# module-mp7740.net
KiCad netlist of a schematic drawn in EAGLE
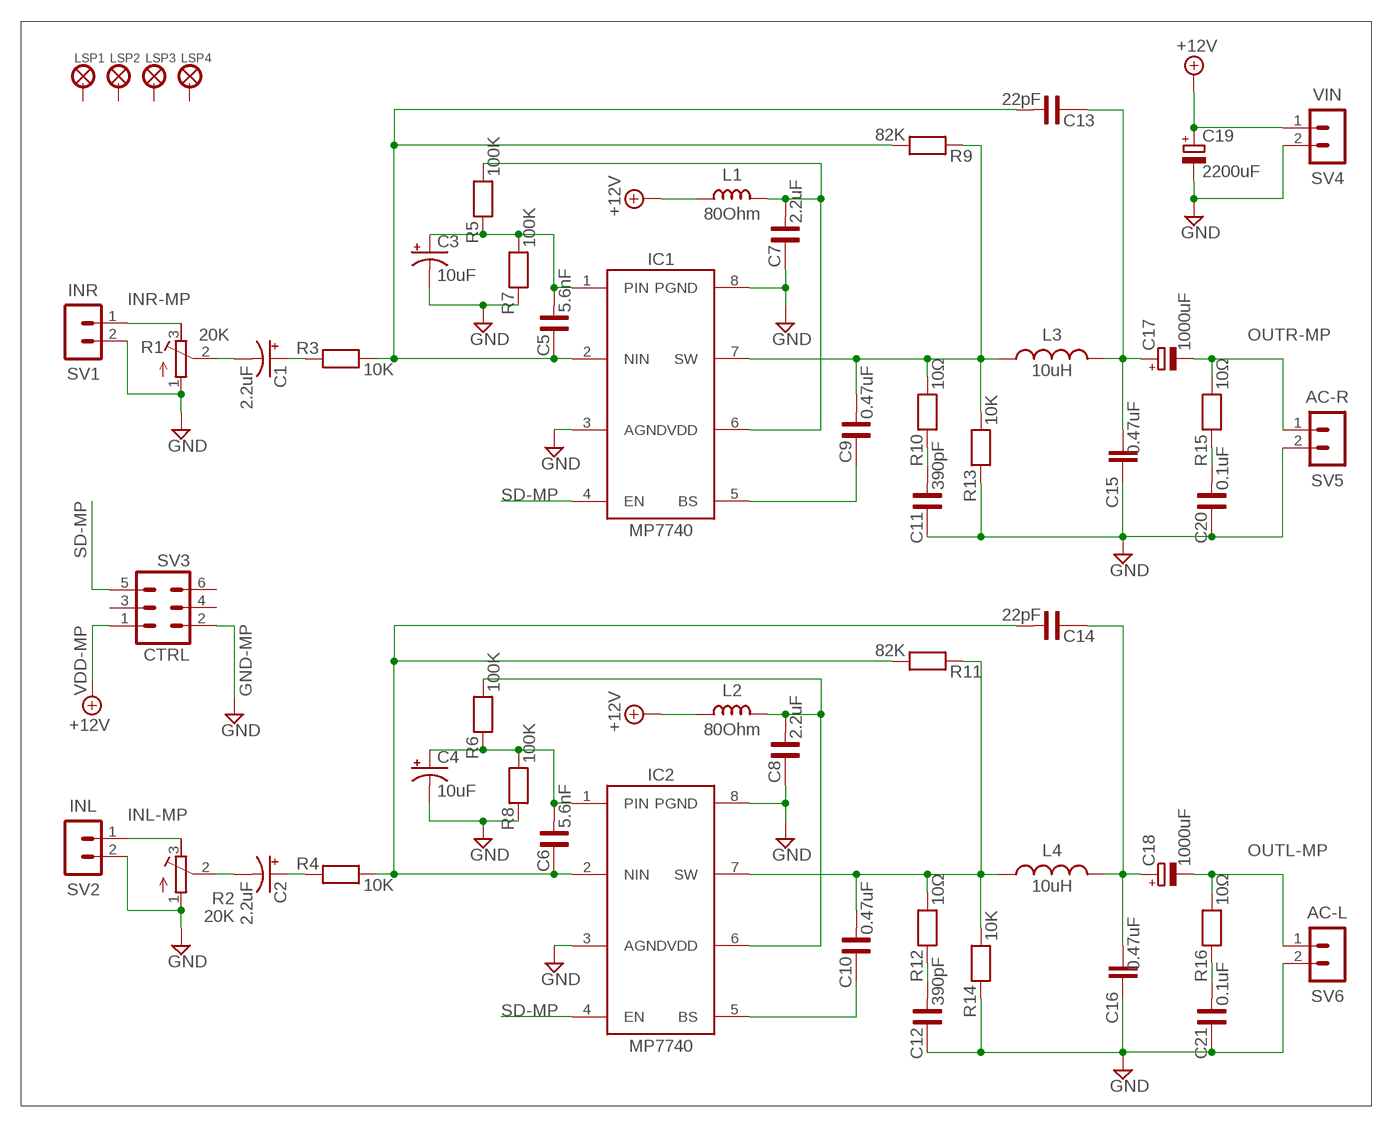
[diagram p0: schematic, sheet 1]

(export (version "E")
  (design (tool "Eeschema 10.0.6"))
  (components
    (comp (ref "C1")
      (value "2.2uF")
      (footprint "eagle-import:E2-5")
      (libsource (lib "eagle-import") (part "CPOL-USE2-5"))
    )
    (comp (ref "C2")
      (value "2.2uF")
      (footprint "eagle-import:E2-5")
      (libsource (lib "eagle-import") (part "CPOL-USE2-5"))
    )
    (comp (ref "C3")
      (value "10uF")
      (footprint "eagle-import:E2-5")
      (libsource (lib "eagle-import") (part "CPOL-USE2-5"))
    )
    (comp (ref "C4")
      (value "10uF")
      (footprint "eagle-import:E2-5")
      (libsource (lib "eagle-import") (part "CPOL-USE2-5"))
    )
    (comp (ref "C5")
      (value "5.6nF")
      (footprint "eagle-import:C0805")
      (libsource (lib "eagle-import") (part "C-US0805"))
    )
    (comp (ref "C6")
      (value "5.6nF")
      (footprint "eagle-import:C0805")
      (libsource (lib "eagle-import") (part "C-US0805"))
    )
    (comp (ref "C7")
      (value "2.2uF")
      (footprint "eagle-import:C1206")
      (libsource (lib "eagle-import") (part "C-US1206"))
    )
    (comp (ref "C8")
      (value "2.2uF")
      (footprint "eagle-import:C1206")
      (libsource (lib "eagle-import") (part "C-US1206"))
    )
    (comp (ref "C9")
      (value "0.47uF")
      (footprint "eagle-import:C0805")
      (libsource (lib "eagle-import") (part "C-US0805"))
    )
    (comp (ref "C10")
      (value "0.47uF")
      (footprint "eagle-import:C0805")
      (libsource (lib "eagle-import") (part "C-US0805"))
    )
    (comp (ref "C11")
      (value "390pF")
      (footprint "eagle-import:C0805")
      (libsource (lib "eagle-import") (part "C-US0805"))
    )
    (comp (ref "C12")
      (value "390pF")
      (footprint "eagle-import:C0805")
      (libsource (lib "eagle-import") (part "C-US0805"))
    )
    (comp (ref "C13")
      (value "22pF")
      (footprint "eagle-import:C0805")
      (libsource (lib "eagle-import") (part "C-US0805"))
    )
    (comp (ref "C14")
      (value "22pF")
      (footprint "eagle-import:C0805")
      (libsource (lib "eagle-import") (part "C-US0805"))
    )
    (comp (ref "C15")
      (value "0.47uF")
      (footprint "eagle-import:C050-050X075")
      (libsource (lib "eagle-import") (part "C-EU050-050X075"))
    )
    (comp (ref "C16")
      (value "0.47uF")
      (footprint "eagle-import:C050-050X075")
      (libsource (lib "eagle-import") (part "C-EU050-050X075"))
    )
    (comp (ref "C17")
      (value "1000uF")
      (footprint "eagle-import:E5-13")
      (libsource (lib "eagle-import") (part "CPOL-EUE5-13"))
    )
    (comp (ref "C18")
      (value "1000uF")
      (footprint "eagle-import:E5-13")
      (libsource (lib "eagle-import") (part "CPOL-EUE5-13"))
    )
    (comp (ref "C19")
      (value "2200uF")
      (footprint "eagle-import:E7,5-16")
      (libsource (lib "eagle-import") (part "CPOL-EUE7.5-16"))
    )
    (comp (ref "C20")
      (value "0.1uF")
      (footprint "eagle-import:C0805")
      (libsource (lib "eagle-import") (part "C-US0805"))
    )
    (comp (ref "C21")
      (value "0.1uF")
      (footprint "eagle-import:C0805")
      (libsource (lib "eagle-import") (part "C-US0805"))
    )
    (comp (ref "IC1")
      (value "MP7740")
      (footprint "eagle-import:SOIC-8")
      (libsource (lib "eagle-import") (part "MP7740"))
    )
    (comp (ref "IC2")
      (value "MP7740")
      (footprint "eagle-import:SOIC-8")
      (libsource (lib "eagle-import") (part "MP7740"))
    )
    (comp (ref "L1")
      (value "80Ohm")
      (footprint "eagle-import:L0805")
      (libsource (lib "eagle-import") (part "L-USL0805"))
    )
    (comp (ref "L2")
      (value "80Ohm")
      (footprint "eagle-import:L0805")
      (libsource (lib "eagle-import") (part "L-USL0805"))
    )
    (comp (ref "L3")
      (value "10uH")
      (footprint "eagle-import:6000-XXXX-RC")
      (libsource (lib "eagle-import") (part "L-US6000-XXX-RC"))
    )
    (comp (ref "L4")
      (value "10uH")
      (footprint "eagle-import:6000-XXXX-RC")
      (libsource (lib "eagle-import") (part "L-US6000-XXX-RC"))
    )
    (comp (ref "LSP1")
      (value "LSP27")
      (footprint "eagle-import:LSP27")
      (libsource (lib "eagle-import") (part "LSP27"))
    )
    (comp (ref "LSP2")
      (value "LSP27")
      (footprint "eagle-import:LSP27")
      (libsource (lib "eagle-import") (part "LSP27"))
    )
    (comp (ref "LSP3")
      (value "LSP27")
      (footprint "eagle-import:LSP27")
      (libsource (lib "eagle-import") (part "LSP27"))
    )
    (comp (ref "LSP4")
      (value "LSP27")
      (footprint "eagle-import:LSP27")
      (libsource (lib "eagle-import") (part "LSP27"))
    )
    (comp (ref "R1")
      (value "20K")
      (footprint "eagle-import:PV32H")
      (libsource (lib "eagle-import") (part "PV32H"))
    )
    (comp (ref "R2")
      (value "20K")
      (footprint "eagle-import:PV32H")
      (libsource (lib "eagle-import") (part "PV32H"))
    )
    (comp (ref "R3")
      (value "10K")
      (footprint "eagle-import:R0805")
      (libsource (lib "eagle-import") (part "R-US0805"))
    )
    (comp (ref "R4")
      (value "10K")
      (footprint "eagle-import:R0805")
      (libsource (lib "eagle-import") (part "R-US0805"))
    )
    (comp (ref "R5")
      (value "100K")
      (footprint "eagle-import:R0805")
      (libsource (lib "eagle-import") (part "R-US0805"))
    )
    (comp (ref "R6")
      (value "100K")
      (footprint "eagle-import:R0805")
      (libsource (lib "eagle-import") (part "R-US0805"))
    )
    (comp (ref "R7")
      (value "100K")
      (footprint "eagle-import:R0805")
      (libsource (lib "eagle-import") (part "R-US0805"))
    )
    (comp (ref "R8")
      (value "100K")
      (footprint "eagle-import:R0805")
      (libsource (lib "eagle-import") (part "R-US0805"))
    )
    (comp (ref "R9")
      (value "82K")
      (footprint "eagle-import:R0805")
      (libsource (lib "eagle-import") (part "R-US0805"))
    )
    (comp (ref "R10")
      (value "10Ω")
      (footprint "eagle-import:R0805")
      (libsource (lib "eagle-import") (part "R-US0805"))
    )
    (comp (ref "R11")
      (value "82K")
      (footprint "eagle-import:R0805")
      (libsource (lib "eagle-import") (part "R-US0805"))
    )
    (comp (ref "R12")
      (value "10Ω")
      (footprint "eagle-import:R0805")
      (libsource (lib "eagle-import") (part "R-US0805"))
    )
    (comp (ref "R13")
      (value "10K")
      (footprint "eagle-import:R0805")
      (libsource (lib "eagle-import") (part "R-US0805"))
    )
    (comp (ref "R14")
      (value "10K")
      (footprint "eagle-import:R0805")
      (libsource (lib "eagle-import") (part "R-US0805"))
    )
    (comp (ref "R15")
      (value "10Ω")
      (footprint "eagle-import:R0805")
      (libsource (lib "eagle-import") (part "R-US0805"))
    )
    (comp (ref "R16")
      (value "10Ω")
      (footprint "eagle-import:R0805")
      (libsource (lib "eagle-import") (part "R-US0805"))
    )
    (comp (ref "SV1")
      (value "INR")
      (footprint "eagle-import:MA02-1-GREEN")
      (libsource (lib "eagle-import") (part "MA02-1GREEN"))
    )
    (comp (ref "SV2")
      (value "INL")
      (footprint "eagle-import:MA02-1-GREEN")
      (libsource (lib "eagle-import") (part "MA02-1GREEN"))
    )
    (comp (ref "SV3")
      (value "CTRL")
      (footprint "eagle-import:MA03-2")
      (libsource (lib "eagle-import") (part "MA03-2PL"))
    )
    (comp (ref "SV4")
      (value "VIN")
      (footprint "eagle-import:MA02-1-GREEN")
      (libsource (lib "eagle-import") (part "MA02-1GREEN"))
    )
    (comp (ref "SV5")
      (value "AC-R")
      (footprint "eagle-import:MA02-1-GREEN")
      (libsource (lib "eagle-import") (part "MA02-1GREEN"))
    )
    (comp (ref "SV6")
      (value "AC-L")
      (footprint "eagle-import:MA02-1-GREEN")
      (libsource (lib "eagle-import") (part "MA02-1GREEN"))
    )
  )
  (nets
    (net (code "1") (name "+12V") (class "Default")
      (node (ref "C19") (pin "+") (pinfunction "+_+") (pintype "passive"))
      (node (ref "L1") (pin "1") (pinfunction "1_1") (pintype "passive"))
      (node (ref "L2") (pin "1") (pinfunction "1_1") (pintype "passive"))
      (node (ref "SV3") (pin "1") (pinfunction "1_1") (pintype "passive"))
      (node (ref "SV4") (pin "1") (pinfunction "1_1") (pintype "passive"))
    )
    (net (code "2") (name "/INL-MP") (class "Default")
      (node (ref "R2") (pin "3") (pinfunction "3_3") (pintype "passive"))
      (node (ref "SV2") (pin "1") (pinfunction "1_1") (pintype "passive"))
    )
    (net (code "3") (name "/INR-MP") (class "Default")
      (node (ref "R1") (pin "3") (pinfunction "3_3") (pintype "passive"))
      (node (ref "SV1") (pin "1") (pinfunction "1_1") (pintype "passive"))
    )
    (net (code "4") (name "/OUTL-MP") (class "Default")
      (node (ref "C18") (pin "-") (pinfunction "-_-") (pintype "passive"))
      (node (ref "R16") (pin "2") (pinfunction "2_2") (pintype "passive"))
      (node (ref "SV6") (pin "1") (pinfunction "1_1") (pintype "passive"))
    )
    (net (code "5") (name "/OUTR-MP") (class "Default")
      (node (ref "C17") (pin "-") (pinfunction "-_-") (pintype "passive"))
      (node (ref "R15") (pin "2") (pinfunction "2_2") (pintype "passive"))
      (node (ref "SV5") (pin "1") (pinfunction "1_1") (pintype "passive"))
    )
    (net (code "6") (name "/SD-MP") (class "Default")
      (node (ref "IC1") (pin "4") (pinfunction "EN_4") (pintype "bidirectional"))
      (node (ref "IC2") (pin "4") (pinfunction "EN_4") (pintype "bidirectional"))
      (node (ref "SV3") (pin "5") (pinfunction "5_5") (pintype "passive"))
    )
    (net (code "7") (name "GND") (class "Default")
      (node (ref "C11") (pin "1") (pinfunction "1_1") (pintype "passive"))
      (node (ref "C12") (pin "1") (pinfunction "1_1") (pintype "passive"))
      (node (ref "C15") (pin "1") (pinfunction "1_1") (pintype "passive"))
      (node (ref "C16") (pin "1") (pinfunction "1_1") (pintype "passive"))
      (node (ref "C19") (pin "-") (pinfunction "-_-") (pintype "passive"))
      (node (ref "C20") (pin "1") (pinfunction "1_1") (pintype "passive"))
      (node (ref "C21") (pin "1") (pinfunction "1_1") (pintype "passive"))
      (node (ref "C3") (pin "-") (pinfunction "-_-") (pintype "passive"))
      (node (ref "C4") (pin "-") (pinfunction "-_-") (pintype "passive"))
      (node (ref "C7") (pin "1") (pinfunction "1_1") (pintype "passive"))
      (node (ref "C8") (pin "1") (pinfunction "1_1") (pintype "passive"))
      (node (ref "IC1") (pin "3") (pinfunction "AGND_3") (pintype "bidirectional"))
      (node (ref "IC1") (pin "8") (pinfunction "PGND_8") (pintype "bidirectional"))
      (node (ref "IC2") (pin "3") (pinfunction "AGND_3") (pintype "bidirectional"))
      (node (ref "IC2") (pin "8") (pinfunction "PGND_8") (pintype "bidirectional"))
      (node (ref "R1") (pin "1") (pinfunction "1_1") (pintype "passive"))
      (node (ref "R13") (pin "1") (pinfunction "1_1") (pintype "passive"))
      (node (ref "R14") (pin "1") (pinfunction "1_1") (pintype "passive"))
      (node (ref "R2") (pin "1") (pinfunction "1_1") (pintype "passive"))
      (node (ref "R7") (pin "1") (pinfunction "1_1") (pintype "passive"))
      (node (ref "R8") (pin "1") (pinfunction "1_1") (pintype "passive"))
      (node (ref "SV1") (pin "2") (pinfunction "2_2") (pintype "passive"))
      (node (ref "SV2") (pin "2") (pinfunction "2_2") (pintype "passive"))
      (node (ref "SV3") (pin "2") (pinfunction "2_2") (pintype "passive"))
      (node (ref "SV4") (pin "2") (pinfunction "2_2") (pintype "passive"))
      (node (ref "SV5") (pin "2") (pinfunction "2_2") (pintype "passive"))
      (node (ref "SV6") (pin "2") (pinfunction "2_2") (pintype "passive"))
    )
    (net (code "8") (name "Net-(C1-Pad+)") (class "Default")
      (node (ref "C1") (pin "+") (pinfunction "+_+") (pintype "passive"))
      (node (ref "R3") (pin "1") (pinfunction "1_1") (pintype "passive"))
    )
    (net (code "9") (name "Net-(C1-Pad-)") (class "Default")
      (node (ref "C1") (pin "-") (pinfunction "-_-") (pintype "passive"))
      (node (ref "R1") (pin "2") (pinfunction "2_2") (pintype "passive"))
    )
    (net (code "10") (name "Net-(C2-Pad+)") (class "Default")
      (node (ref "C2") (pin "+") (pinfunction "+_+") (pintype "passive"))
      (node (ref "R4") (pin "1") (pinfunction "1_1") (pintype "passive"))
    )
    (net (code "11") (name "Net-(C2-Pad-)") (class "Default")
      (node (ref "C2") (pin "-") (pinfunction "-_-") (pintype "passive"))
      (node (ref "R2") (pin "2") (pinfunction "2_2") (pintype "passive"))
    )
    (net (code "12") (name "Net-(C11-Pad2)") (class "Default")
      (node (ref "C11") (pin "2") (pinfunction "2_2") (pintype "passive"))
      (node (ref "R10") (pin "1") (pinfunction "1_1") (pintype "passive"))
    )
    (net (code "13") (name "Net-(C12-Pad2)") (class "Default")
      (node (ref "C12") (pin "2") (pinfunction "2_2") (pintype "passive"))
      (node (ref "R12") (pin "1") (pinfunction "1_1") (pintype "passive"))
    )
    (net (code "14") (name "Net-(C13-Pad1)") (class "Default")
      (node (ref "C13") (pin "1") (pinfunction "1_1") (pintype "passive"))
      (node (ref "C15") (pin "2") (pinfunction "2_2") (pintype "passive"))
      (node (ref "C17") (pin "+") (pinfunction "+_+") (pintype "passive"))
      (node (ref "L3") (pin "2") (pinfunction "2_2") (pintype "passive"))
    )
    (net (code "15") (name "Net-(C14-Pad1)") (class "Default")
      (node (ref "C14") (pin "1") (pinfunction "1_1") (pintype "passive"))
      (node (ref "C16") (pin "2") (pinfunction "2_2") (pintype "passive"))
      (node (ref "C18") (pin "+") (pinfunction "+_+") (pintype "passive"))
      (node (ref "L4") (pin "2") (pinfunction "2_2") (pintype "passive"))
    )
    (net (code "16") (name "Net-(C20-Pad2)") (class "Default")
      (node (ref "C20") (pin "2") (pinfunction "2_2") (pintype "passive"))
      (node (ref "R15") (pin "1") (pinfunction "1_1") (pintype "passive"))
    )
    (net (code "17") (name "Net-(C21-Pad2)") (class "Default")
      (node (ref "C21") (pin "2") (pinfunction "2_2") (pintype "passive"))
      (node (ref "R16") (pin "1") (pinfunction "1_1") (pintype "passive"))
    )
    (net (code "18") (name "Net-(IC1-BS)") (class "Default")
      (node (ref "C9") (pin "1") (pinfunction "1_1") (pintype "passive"))
      (node (ref "IC1") (pin "5") (pinfunction "BS_5") (pintype "bidirectional"))
    )
    (net (code "19") (name "Net-(IC1-NIN)") (class "Default")
      (node (ref "C13") (pin "2") (pinfunction "2_2") (pintype "passive"))
      (node (ref "C5") (pin "1") (pinfunction "1_1") (pintype "passive"))
      (node (ref "IC1") (pin "2") (pinfunction "NIN_2") (pintype "bidirectional"))
      (node (ref "R3") (pin "2") (pinfunction "2_2") (pintype "passive"))
      (node (ref "R9") (pin "2") (pinfunction "2_2") (pintype "passive"))
    )
    (net (code "20") (name "Net-(IC1-PIN)") (class "Default")
      (node (ref "C3") (pin "+") (pinfunction "+_+") (pintype "passive"))
      (node (ref "C5") (pin "2") (pinfunction "2_2") (pintype "passive"))
      (node (ref "IC1") (pin "1") (pinfunction "PIN_1") (pintype "bidirectional"))
      (node (ref "R5") (pin "1") (pinfunction "1_1") (pintype "passive"))
      (node (ref "R7") (pin "2") (pinfunction "2_2") (pintype "passive"))
    )
    (net (code "21") (name "Net-(IC1-SW)") (class "Default")
      (node (ref "C9") (pin "2") (pinfunction "2_2") (pintype "passive"))
      (node (ref "IC1") (pin "7") (pinfunction "SW_7") (pintype "bidirectional"))
      (node (ref "L3") (pin "1") (pinfunction "1_1") (pintype "passive"))
      (node (ref "R10") (pin "2") (pinfunction "2_2") (pintype "passive"))
      (node (ref "R13") (pin "2") (pinfunction "2_2") (pintype "passive"))
      (node (ref "R9") (pin "1") (pinfunction "1_1") (pintype "passive"))
    )
    (net (code "22") (name "Net-(IC1-VDD)") (class "Default")
      (node (ref "C7") (pin "2") (pinfunction "2_2") (pintype "passive"))
      (node (ref "IC1") (pin "6") (pinfunction "VDD_6") (pintype "bidirectional"))
      (node (ref "L1") (pin "2") (pinfunction "2_2") (pintype "passive"))
      (node (ref "R5") (pin "2") (pinfunction "2_2") (pintype "passive"))
    )
    (net (code "23") (name "Net-(IC2-BS)") (class "Default")
      (node (ref "C10") (pin "1") (pinfunction "1_1") (pintype "passive"))
      (node (ref "IC2") (pin "5") (pinfunction "BS_5") (pintype "bidirectional"))
    )
    (net (code "24") (name "Net-(IC2-NIN)") (class "Default")
      (node (ref "C14") (pin "2") (pinfunction "2_2") (pintype "passive"))
      (node (ref "C6") (pin "1") (pinfunction "1_1") (pintype "passive"))
      (node (ref "IC2") (pin "2") (pinfunction "NIN_2") (pintype "bidirectional"))
      (node (ref "R11") (pin "2") (pinfunction "2_2") (pintype "passive"))
      (node (ref "R4") (pin "2") (pinfunction "2_2") (pintype "passive"))
    )
    (net (code "25") (name "Net-(IC2-PIN)") (class "Default")
      (node (ref "C4") (pin "+") (pinfunction "+_+") (pintype "passive"))
      (node (ref "C6") (pin "2") (pinfunction "2_2") (pintype "passive"))
      (node (ref "IC2") (pin "1") (pinfunction "PIN_1") (pintype "bidirectional"))
      (node (ref "R6") (pin "1") (pinfunction "1_1") (pintype "passive"))
      (node (ref "R8") (pin "2") (pinfunction "2_2") (pintype "passive"))
    )
    (net (code "26") (name "Net-(IC2-SW)") (class "Default")
      (node (ref "C10") (pin "2") (pinfunction "2_2") (pintype "passive"))
      (node (ref "IC2") (pin "7") (pinfunction "SW_7") (pintype "bidirectional"))
      (node (ref "L4") (pin "1") (pinfunction "1_1") (pintype "passive"))
      (node (ref "R11") (pin "1") (pinfunction "1_1") (pintype "passive"))
      (node (ref "R12") (pin "2") (pinfunction "2_2") (pintype "passive"))
      (node (ref "R14") (pin "2") (pinfunction "2_2") (pintype "passive"))
    )
    (net (code "27") (name "Net-(IC2-VDD)") (class "Default")
      (node (ref "C8") (pin "2") (pinfunction "2_2") (pintype "passive"))
      (node (ref "IC2") (pin "6") (pinfunction "VDD_6") (pintype "bidirectional"))
      (node (ref "L2") (pin "2") (pinfunction "2_2") (pintype "passive"))
      (node (ref "R6") (pin "2") (pinfunction "2_2") (pintype "passive"))
    )
    (net (code "28") (name "unconnected-(LSP1-PadMP)") (class "Default")
      (node (ref "LSP1") (pin "MP") (pinfunction "MP_MP") (pintype "passive"))
    )
    (net (code "29") (name "unconnected-(LSP2-PadMP)") (class "Default")
      (node (ref "LSP2") (pin "MP") (pinfunction "MP_MP") (pintype "passive"))
    )
    (net (code "30") (name "unconnected-(LSP3-PadMP)") (class "Default")
      (node (ref "LSP3") (pin "MP") (pinfunction "MP_MP") (pintype "passive"))
    )
    (net (code "31") (name "unconnected-(LSP4-PadMP)") (class "Default")
      (node (ref "LSP4") (pin "MP") (pinfunction "MP_MP") (pintype "passive"))
    )
    (net (code "32") (name "unconnected-(SV3-Pad3)") (class "Default")
      (node (ref "SV3") (pin "3") (pinfunction "3_3") (pintype "passive"))
    )
    (net (code "33") (name "unconnected-(SV3-Pad4)") (class "Default")
      (node (ref "SV3") (pin "4") (pinfunction "4_4") (pintype "passive"))
    )
    (net (code "34") (name "unconnected-(SV3-Pad6)") (class "Default")
      (node (ref "SV3") (pin "6") (pinfunction "6_6") (pintype "passive"))
    )
  )
)
